# temp_controller_01.net
KiCad netlist of a schematic drawn in Altium Designer
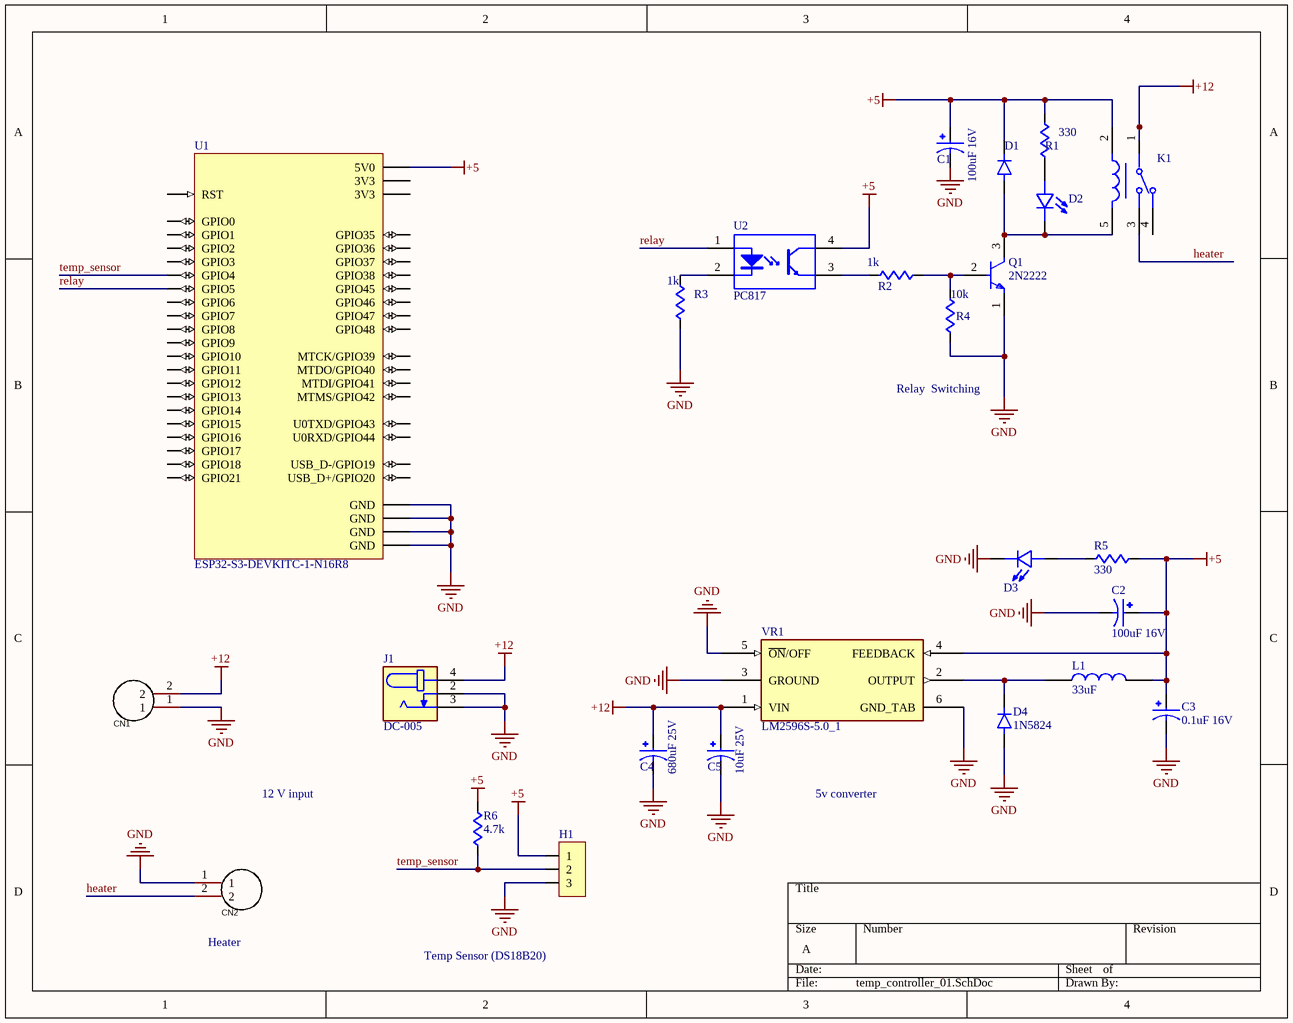
[diagram p0: temp_controller_01.SchDoc]

(export (version "E")
  (design (tool "Eeschema 10.0.6"))
  (components
    (comp (ref "C1")
      (value "100uF 16V")
      (footprint "100uF  16V")
      (description "CAP ALUM 100uF 16V RADIAL TH")
      (fields (field (name "MP") "EEU-FR1E221B") (field (name "MF") "Panasonic Electronic Components"))
      (libsource (lib "Capacitor TH") (part "100uF 16V"))
    )
    (comp (ref "C2")
      (value "100uF 16V")
      (footprint "100uF  16V")
      (description "CAP ALUM 100uF 16V RADIAL TH")
      (fields (field (name "MP") "EEU-FR1E221B") (field (name "MF") "Panasonic Electronic Components"))
      (libsource (lib "") (part "100uF 16V_1"))
    )
    (comp (ref "C3")
      (value "0.1uF 16V")
      (footprint "0.1uF 16V")
      (description "Cap 0.1uF 16VRADIAL TH")
      (fields (field (name "MP") "EEU-FR1E221B") (field (name "MF") "Panasonic Electronic Components"))
      (libsource (lib "Capacitor TH") (part "0.1uF 16V"))
    )
    (comp (ref "C4")
      (value "680uF 25V")
      (footprint "Capacitor TH:680uF 25V")
      (description "Cap 680uF 25V RADIAL TH")
      (fields (field (name "MP") "EEU-FR1E221B") (field (name "MF") "Panasonic Electronic Components"))
      (libsource (lib "Capacitor TH") (part "680uF 25V"))
    )
    (comp (ref "C5")
      (value "10uF 25V")
      (footprint "Capacitor TH:10 uF 25V")
      (description "Cap 10uF 25V RADIAL TH")
      (fields (field (name "MP") "EEU-FR1E221B") (field (name "MF") "Panasonic Electronic Components"))
      (libsource (lib "Capacitor TH") (part "10uF 25V"))
    )
    (comp (ref "CN1")
      (value "WJ2EDGRC-5.08-2P")
      (footprint "Terminal Block P5.08-2P")
      (fields (field (name "MANUFACTURER") "KANGNEX(康奈克斯电气)"))
      (libsource (lib "Terminal Block P5.08-2P") (part "WJ2EDGRC-5.08-2P"))
    )
    (comp (ref "CN2")
      (value "WJ2EDGRC-5.08-2P")
      (footprint "Terminal Block P5.08-2P")
      (fields (field (name "MANUFACTURER") "KANGNEX(康奈克斯电气)"))
      (libsource (lib "Terminal Block P5.08-2P") (part "WJ2EDGRC-5.08-2P"))
    )
    (comp (ref "D1")
      (value "1N4007-T")
      (footprint "DIOAD780W78L463D236")
      (description "Diode Standard 1A 1000V 1Vf DO41 ¦ Diodes Inc 1N4007-T")
      (fields (field (name "MF") "Diodes Incorporated"))
      (libsource (lib "1N4007-T") (part "1N4007-T"))
    )
    (comp (ref "D2")
      (value "L08R5000Q1")
      (footprint "LEDRD254W57D500H1070")
      (fields (field (name "MF") "LED Technology"))
      (libsource (lib "LED 3mm") (part "L08R5000Q1"))
    )
    (comp (ref "D3")
      (value "L08R5000Q1")
      (footprint "LEDRD254W57D500H1070")
      (fields (field (name "MF") "LED Technology"))
      (libsource (lib "LED 3mm") (part "L08R5000Q1"))
    )
    (comp (ref "D4")
      (value "1N5824")
      (footprint "DIOAD1898W129L762D1143")
      (description "Diode Schottky 30V 5A Through Hole Axial")
      (fields (field (name "MF") "Microsemi Corporation"))
      (libsource (lib "1N5824") (part "1N5824"))
    )
    (comp (ref "H1")
      (value "Header 1x3")
      (footprint "Header 1x3 male")
      (libsource (lib "Pin Header") (part "Header 1x3"))
    )
    (comp (ref "J1")
      (value "DC-005")
      (footprint "NINIGI_DC-005")
      (description "DC Jack")
      (libsource (lib "DC-005") (part "DC-005"))
    )
    (comp (ref "K1")
      (value "G5LE-14-DC5")
      (footprint "FP-G5LE-14-DC5-MFG")
      (description "RELAY GEN PURPOSE SPDT 10A 5V")
      (fields
        (field (name "OCTOPART") "https://octopart.com/g5le-14-dc5-omron-28829")
        (field (name "MANUFACTURER") "Omron")
      )
      (libsource (lib "Relay 5V TH") (part "CMP-08822-000008-1"))
    )
    (comp (ref "L1")
      (value "33uF")
      (footprint "33uF TH  Radial")
      (description "Inductor ¦ 33 uH ¦ TH")
      (fields (field (name "MP") "HCTI-33-11.7") (field (name "MF") "Signal Transformer"))
      (libsource (lib "HCTI-33-11.7") (part "HCTI-33-11.7"))
    )
    (comp (ref "Q1")
      (value "2N2222")
      (footprint "FP-JAN2N2222A-MFG")
      (description "TRANS NPN 50V 0.8A TO218")
      (libsource (lib "2N2222") (part "CMP-06366-000013-1"))
    )
    (comp (ref "R1")
      (value "330")
      (footprint "RESA60-630X240")
      (description "Axial Resistor,")
      (fields (field (name "TOLERANCE") "1%"))
      (libsource (lib "Resistor Generic") (part "CMP-1659-00075-1"))
    )
    (comp (ref "R2")
      (value "1k")
      (footprint "RESA60-630X240")
      (description "Axial Resistor,")
      (fields (field (name "TOLERANCE") "1%"))
      (libsource (lib "Resistor Generic") (part "CMP-1659-00075-1"))
    )
    (comp (ref "R3")
      (value "1k")
      (footprint "RESA60-630X240")
      (description "Axial Resistor,")
      (fields (field (name "TOLERANCE") "1%"))
      (libsource (lib "Resistor Generic") (part "CMP-1659-00075-1"))
    )
    (comp (ref "R4")
      (value "10k")
      (footprint "RESA60-630X240")
      (description "Axial Resistor,")
      (fields (field (name "TOLERANCE") "1%"))
      (libsource (lib "Resistor Generic") (part "CMP-1659-00075-1"))
    )
    (comp (ref "R5")
      (value "330")
      (footprint "RESA60-630X240")
      (description "Axial Resistor,")
      (fields (field (name "TOLERANCE") "1%"))
      (libsource (lib "Resistor Generic") (part "CMP-1659-00075-1"))
    )
    (comp (ref "R6")
      (value "4.7k")
      (footprint "RESA60-630X240")
      (description "Axial Resistor,")
      (fields (field (name "TOLERANCE") "1%"))
      (libsource (lib "Resistor Generic") (part "CMP-1659-00075-1_1"))
    )
    (comp (ref "U1")
      (value "ESP32-S3-DEVKITC-1-N16R8")
      (footprint "XCVR_ESP32-S3-DEVKITC-1-N8R2")
      (fields (field (name "MF") "Espressif Systems") (field (name "MP") "ESP32-S3-DEVKITC-1-N8R2"))
      (libsource (lib "ESP32-S3-DEVKITC-1-N8R2") (part "ESP32-S3-DEVKITC-1-N8R2"))
    )
    (comp (ref "U2")
      (value "PC817")
      (footprint "LTST-LTV-817-4")
      (fields (field (name "MANUFACTURER") "Lite-On"))
      (libsource (lib "PC817") (part "CMP-2000-06632-1"))
    )
    (comp (ref "VR1")
      (value "LM2596S-5.0_1")
      (footprint "TO170P1524X483-6N")
      (description "SIMPLE SWITCHER&reg; 4.5V to 40V, 3A Low Component Count Step-Down Regulator")
      (fields (field (name "MP") "LM2596S-5.0/NOPB") (field (name "MF") "Texas Instruments"))
      (libsource (lib "LM2596S-5.0") (part "LM2596S-5.0_1"))
    )
  )
  (nets
    (net (code "1") (name "+5") (class "Default")
      (node (ref "C1") (pin "P") (pinfunction "P_P") (pintype "passive"))
      (node (ref "C2") (pin "P") (pinfunction "P_P") (pintype "passive"))
      (node (ref "C3") (pin "P") (pinfunction "P_P") (pintype "passive"))
      (node (ref "D1") (pin "K") (pinfunction "K_K") (pintype "passive"))
      (node (ref "H1") (pin "1") (pinfunction "1_1") (pintype "passive"))
      (node (ref "K1") (pin "2") (pinfunction "2_2") (pintype "passive"))
      (node (ref "L1") (pin "2") (pinfunction "2_2") (pintype "passive"))
      (node (ref "R1") (pin "1") (pinfunction "1_1") (pintype "passive"))
      (node (ref "R5") (pin "2") (pinfunction "2_2") (pintype "passive"))
      (node (ref "R6") (pin "1") (pinfunction "1_1") (pintype "passive"))
      (node (ref "U1") (pin "J1_21") (pinfunction "5V0_J1_21") (pintype "power_in"))
      (node (ref "U2") (pin "4") (pinfunction "COLLECTOR_4") (pintype "passive"))
      (node (ref "VR1") (pin "4") (pinfunction "FEEDBACK_4") (pintype "input"))
    )
    (net (code "2") (name "+12") (class "Default")
      (node (ref "C4") (pin "P") (pinfunction "P_P") (pintype "passive"))
      (node (ref "C5") (pin "P") (pinfunction "P_P") (pintype "passive"))
      (node (ref "CN1") (pin "2") (pinfunction "2_2") (pintype "passive"))
      (node (ref "J1") (pin "4") (pinfunction "2_4") (pintype "passive"))
      (node (ref "K1") (pin "1") (pinfunction "1_1") (pintype "passive"))
      (node (ref "VR1") (pin "1") (pinfunction "VIN_1") (pintype "input"))
    )
    (net (code "3") (name "/heater") (class "Default")
      (node (ref "CN2") (pin "2") (pinfunction "2_2") (pintype "passive"))
      (node (ref "K1") (pin "3") (pinfunction "3_3") (pintype "passive"))
    )
    (net (code "4") (name "/relay") (class "Default")
      (node (ref "U1") (pin "J1_5") (pinfunction "GPIO5_J1_5") (pintype "bidirectional"))
      (node (ref "U2") (pin "1") (pinfunction "ANODE_1") (pintype "passive"))
    )
    (net (code "5") (name "/temp_sensor") (class "Default")
      (node (ref "H1") (pin "2") (pinfunction "2_2") (pintype "passive"))
      (node (ref "R6") (pin "2") (pinfunction "2_2") (pintype "passive"))
      (node (ref "U1") (pin "J1_4") (pinfunction "GPIO4_J1_4") (pintype "bidirectional"))
    )
    (net (code "6") (name "GND") (class "Default")
      (node (ref "C1") (pin "N") (pinfunction "N_N") (pintype "passive"))
      (node (ref "C2") (pin "N") (pinfunction "N_N") (pintype "passive"))
      (node (ref "C3") (pin "N") (pinfunction "N_N") (pintype "passive"))
      (node (ref "C4") (pin "N") (pinfunction "N_N") (pintype "passive"))
      (node (ref "C5") (pin "N") (pinfunction "N_N") (pintype "passive"))
      (node (ref "CN1") (pin "1") (pinfunction "1_1") (pintype "passive"))
      (node (ref "CN2") (pin "1") (pinfunction "1_1") (pintype "passive"))
      (node (ref "D3") (pin "C") (pinfunction "C_C") (pintype "passive"))
      (node (ref "D4") (pin "A") (pinfunction "A_A") (pintype "passive"))
      (node (ref "H1") (pin "3") (pinfunction "3_3") (pintype "passive"))
      (node (ref "J1") (pin "2") (pinfunction "4_2") (pintype "passive"))
      (node (ref "J1") (pin "3") (pinfunction "5_3") (pintype "passive"))
      (node (ref "Q1") (pin "1") (pinfunction "E_1") (pintype "passive"))
      (node (ref "R3") (pin "2") (pinfunction "2_2") (pintype "passive"))
      (node (ref "R4") (pin "2") (pinfunction "2_2") (pintype "passive"))
      (node (ref "U1") (pin "J1_22") (pinfunction "GND_J1_22") (pintype "power_in"))
      (node (ref "U1") (pin "J3_1") (pinfunction "GND_J3_1") (pintype "power_in"))
      (node (ref "U1") (pin "J3_21") (pinfunction "GND_J3_21") (pintype "power_in"))
      (node (ref "U1") (pin "J3_22") (pinfunction "GND_J3_22") (pintype "power_in"))
      (node (ref "VR1") (pin "3") (pinfunction "GROUND_3") (pintype "power_in"))
      (node (ref "VR1") (pin "5") (pinfunction "~{ON}/OFF_5") (pintype "input"))
      (node (ref "VR1") (pin "6") (pinfunction "GND_TAB_6") (pintype "power_in"))
    )
    (net (code "7") (name "Net-(D2-PadA)") (class "Default")
      (node (ref "D2") (pin "A") (pinfunction "A_A") (pintype "passive"))
      (node (ref "R1") (pin "2") (pinfunction "2_2") (pintype "passive"))
    )
    (net (code "8") (name "Net-(D3-PadA)") (class "Default")
      (node (ref "D3") (pin "A") (pinfunction "A_A") (pintype "passive"))
      (node (ref "R5") (pin "1") (pinfunction "1_1") (pintype "passive"))
    )
    (net (code "9") (name "Net-(D4-K)") (class "Default")
      (node (ref "D4") (pin "C") (pinfunction "K_C") (pintype "passive"))
      (node (ref "L1") (pin "1") (pinfunction "1_1") (pintype "passive"))
      (node (ref "VR1") (pin "2") (pinfunction "OUTPUT_2") (pintype "output"))
    )
    (net (code "10") (name "Net-(Q1-B)") (class "Default")
      (node (ref "Q1") (pin "2") (pinfunction "B_2") (pintype "passive"))
      (node (ref "R2") (pin "1") (pinfunction "1_1") (pintype "passive"))
      (node (ref "R4") (pin "1") (pinfunction "1_1") (pintype "passive"))
    )
    (net (code "11") (name "Net-(Q1-C)") (class "Default")
      (node (ref "D1") (pin "A") (pinfunction "A_A") (pintype "passive"))
      (node (ref "D2") (pin "C") (pinfunction "C_C") (pintype "passive"))
      (node (ref "K1") (pin "5") (pinfunction "5_5") (pintype "passive"))
      (node (ref "Q1") (pin "3") (pinfunction "C_3") (pintype "passive"))
    )
    (net (code "12") (name "Net-(U2-CATHODE)") (class "Default")
      (node (ref "R3") (pin "1") (pinfunction "1_1") (pintype "passive"))
      (node (ref "U2") (pin "2") (pinfunction "CATHODE_2") (pintype "passive"))
    )
    (net (code "13") (name "Net-(U2-EMITTER)") (class "Default")
      (node (ref "R2") (pin "2") (pinfunction "2_2") (pintype "passive"))
      (node (ref "U2") (pin "3") (pinfunction "EMITTER_3") (pintype "passive"))
    )
    (net (code "14") (name "unconnected-(K1-Pad4)") (class "Default")
      (node (ref "K1") (pin "4") (pinfunction "4_4") (pintype "passive"))
    )
    (net (code "15") (name "unconnected-(U1-3V3-PadJ1_1)") (class "Default")
      (node (ref "U1") (pin "J1_1") (pinfunction "3V3_J1_1") (pintype "power_in"))
    )
    (net (code "16") (name "unconnected-(U1-3V3-PadJ1_2)") (class "Default")
      (node (ref "U1") (pin "J1_2") (pinfunction "3V3_J1_2") (pintype "power_in"))
    )
    (net (code "17") (name "unconnected-(U1-GPIO0-PadJ3_14)") (class "Default")
      (node (ref "U1") (pin "J3_14") (pinfunction "GPIO0_J3_14") (pintype "bidirectional"))
    )
    (net (code "18") (name "unconnected-(U1-GPIO1-PadJ3_4)") (class "Default")
      (node (ref "U1") (pin "J3_4") (pinfunction "GPIO1_J3_4") (pintype "bidirectional"))
    )
    (net (code "19") (name "unconnected-(U1-GPIO2-PadJ3_5)") (class "Default")
      (node (ref "U1") (pin "J3_5") (pinfunction "GPIO2_J3_5") (pintype "bidirectional"))
    )
    (net (code "20") (name "unconnected-(U1-GPIO3-PadJ1_13)") (class "Default")
      (node (ref "U1") (pin "J1_13") (pinfunction "GPIO3_J1_13") (pintype "bidirectional"))
    )
    (net (code "21") (name "unconnected-(U1-GPIO6-PadJ1_6)") (class "Default")
      (node (ref "U1") (pin "J1_6") (pinfunction "GPIO6_J1_6") (pintype "bidirectional"))
    )
    (net (code "22") (name "unconnected-(U1-GPIO7-PadJ1_7)") (class "Default")
      (node (ref "U1") (pin "J1_7") (pinfunction "GPIO7_J1_7") (pintype "bidirectional"))
    )
    (net (code "23") (name "unconnected-(U1-GPIO8-PadJ1_12)") (class "Default")
      (node (ref "U1") (pin "J1_12") (pinfunction "GPIO8_J1_12") (pintype "bidirectional"))
    )
    (net (code "24") (name "unconnected-(U1-GPIO9-PadJ1_15)") (class "Default")
      (node (ref "U1") (pin "J1_15") (pinfunction "GPIO9_J1_15") (pintype "bidirectional"))
    )
    (net (code "25") (name "unconnected-(U1-GPIO10-PadJ1_16)") (class "Default")
      (node (ref "U1") (pin "J1_16") (pinfunction "GPIO10_J1_16") (pintype "bidirectional"))
    )
    (net (code "26") (name "unconnected-(U1-GPIO11-PadJ1_17)") (class "Default")
      (node (ref "U1") (pin "J1_17") (pinfunction "GPIO11_J1_17") (pintype "bidirectional"))
    )
    (net (code "27") (name "unconnected-(U1-GPIO12-PadJ1_18)") (class "Default")
      (node (ref "U1") (pin "J1_18") (pinfunction "GPIO12_J1_18") (pintype "bidirectional"))
    )
    (net (code "28") (name "unconnected-(U1-GPIO13-PadJ1_19)") (class "Default")
      (node (ref "U1") (pin "J1_19") (pinfunction "GPIO13_J1_19") (pintype "bidirectional"))
    )
    (net (code "29") (name "unconnected-(U1-GPIO14-PadJ1_20)") (class "Default")
      (node (ref "U1") (pin "J1_20") (pinfunction "GPIO14_J1_20") (pintype "bidirectional"))
    )
    (net (code "30") (name "unconnected-(U1-GPIO15-PadJ1_8)") (class "Default")
      (node (ref "U1") (pin "J1_8") (pinfunction "GPIO15_J1_8") (pintype "bidirectional"))
    )
    (net (code "31") (name "unconnected-(U1-GPIO16-PadJ1_9)") (class "Default")
      (node (ref "U1") (pin "J1_9") (pinfunction "GPIO16_J1_9") (pintype "bidirectional"))
    )
    (net (code "32") (name "unconnected-(U1-GPIO17-PadJ1_10)") (class "Default")
      (node (ref "U1") (pin "J1_10") (pinfunction "GPIO17_J1_10") (pintype "bidirectional"))
    )
    (net (code "33") (name "unconnected-(U1-GPIO18-PadJ1_11)") (class "Default")
      (node (ref "U1") (pin "J1_11") (pinfunction "GPIO18_J1_11") (pintype "bidirectional"))
    )
    (net (code "34") (name "unconnected-(U1-GPIO21-PadJ3_18)") (class "Default")
      (node (ref "U1") (pin "J3_18") (pinfunction "GPIO21_J3_18") (pintype "bidirectional"))
    )
    (net (code "35") (name "unconnected-(U1-GPIO35-PadJ3_13)") (class "Default")
      (node (ref "U1") (pin "J3_13") (pinfunction "GPIO35_J3_13") (pintype "bidirectional"))
    )
    (net (code "36") (name "unconnected-(U1-GPIO36-PadJ3_12)") (class "Default")
      (node (ref "U1") (pin "J3_12") (pinfunction "GPIO36_J3_12") (pintype "bidirectional"))
    )
    (net (code "37") (name "unconnected-(U1-GPIO37-PadJ3_11)") (class "Default")
      (node (ref "U1") (pin "J3_11") (pinfunction "GPIO37_J3_11") (pintype "bidirectional"))
    )
    (net (code "38") (name "unconnected-(U1-GPIO38-PadJ3_10)") (class "Default")
      (node (ref "U1") (pin "J3_10") (pinfunction "GPIO38_J3_10") (pintype "bidirectional"))
    )
    (net (code "39") (name "unconnected-(U1-GPIO45-PadJ3_15)") (class "Default")
      (node (ref "U1") (pin "J3_15") (pinfunction "GPIO45_J3_15") (pintype "bidirectional"))
    )
    (net (code "40") (name "unconnected-(U1-GPIO46-PadJ1_14)") (class "Default")
      (node (ref "U1") (pin "J1_14") (pinfunction "GPIO46_J1_14") (pintype "bidirectional"))
    )
    (net (code "41") (name "unconnected-(U1-GPIO47-PadJ3_17)") (class "Default")
      (node (ref "U1") (pin "J3_17") (pinfunction "GPIO47_J3_17") (pintype "bidirectional"))
    )
    (net (code "42") (name "unconnected-(U1-GPIO48-PadJ3_16)") (class "Default")
      (node (ref "U1") (pin "J3_16") (pinfunction "GPIO48_J3_16") (pintype "bidirectional"))
    )
    (net (code "43") (name "unconnected-(U1-MTCK{slash}GPIO39-PadJ3_9)") (class "Default")
      (node (ref "U1") (pin "J3_9") (pinfunction "MTCK/GPIO39_J3_9") (pintype "bidirectional"))
    )
    (net (code "44") (name "unconnected-(U1-MTDI{slash}GPIO41-PadJ3_7)") (class "Default")
      (node (ref "U1") (pin "J3_7") (pinfunction "MTDI/GPIO41_J3_7") (pintype "bidirectional"))
    )
    (net (code "45") (name "unconnected-(U1-MTDO{slash}GPIO40-PadJ3_8)") (class "Default")
      (node (ref "U1") (pin "J3_8") (pinfunction "MTDO/GPIO40_J3_8") (pintype "bidirectional"))
    )
    (net (code "46") (name "unconnected-(U1-MTMS{slash}GPIO42-PadJ3_6)") (class "Default")
      (node (ref "U1") (pin "J3_6") (pinfunction "MTMS/GPIO42_J3_6") (pintype "bidirectional"))
    )
    (net (code "47") (name "unconnected-(U1-RST-PadJ1_3)") (class "Default")
      (node (ref "U1") (pin "J1_3") (pinfunction "RST_J1_3") (pintype "input"))
    )
    (net (code "48") (name "unconnected-(U1-U0RXD{slash}GPIO44-PadJ3_3)") (class "Default")
      (node (ref "U1") (pin "J3_3") (pinfunction "U0RXD/GPIO44_J3_3") (pintype "bidirectional"))
    )
    (net (code "49") (name "unconnected-(U1-U0TXD{slash}GPIO43-PadJ3_2)") (class "Default")
      (node (ref "U1") (pin "J3_2") (pinfunction "U0TXD/GPIO43_J3_2") (pintype "bidirectional"))
    )
    (net (code "50") (name "unconnected-(U1-USB_D+{slash}GPIO20-PadJ3_19)") (class "Default")
      (node (ref "U1") (pin "J3_19") (pinfunction "USB_D+/GPIO20_J3_19") (pintype "bidirectional"))
    )
    (net (code "51") (name "unconnected-(U1-USB_D-{slash}GPIO19-PadJ3_20)") (class "Default")
      (node (ref "U1") (pin "J3_20") (pinfunction "USB_D-/GPIO19_J3_20") (pintype "bidirectional"))
    )
  )
)
